# MotherBoard.net
KiCad netlist of a schematic drawn in Altium Designer
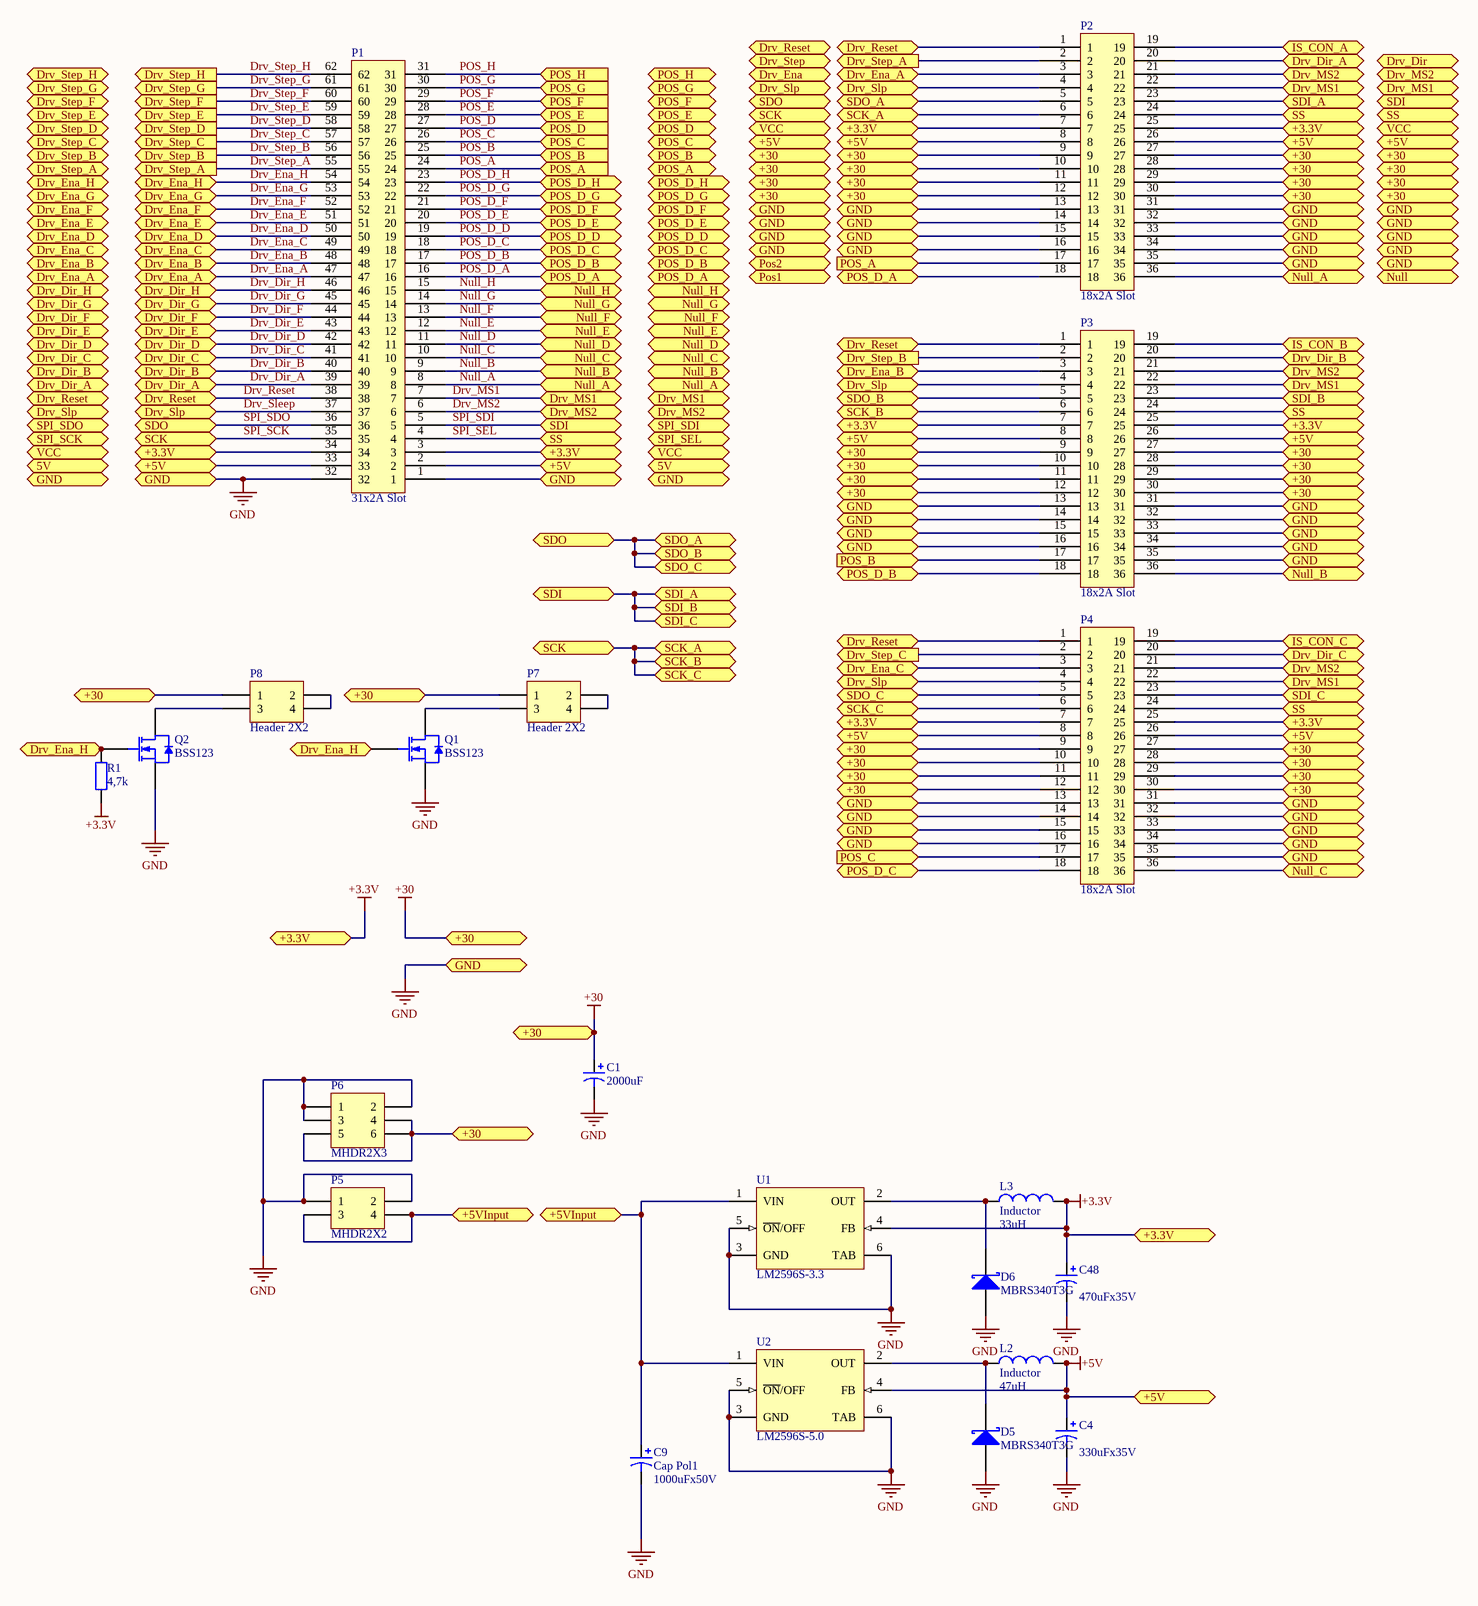
[diagram p0: MotherBoard.SchDoc]

(export (version "E")
  (design (tool "Eeschema 10.0.6"))
  (components
    (comp (ref "C1")
      (value "2000uF")
      (footprint "Cap16x36")
      (description "Polarized Capacitor (Radial)")
      (fields (field (name "Comment") "Cap Pol1") (field (name "PUBLISHER") "Altium Limited"))
      (libsource (lib "Miscellaneous Devices") (part "Cap Pol1"))
    )
    (comp (ref "C4")
      (value "330uFx35V")
      (footprint "Type E")
      (description "Polarized Capacitor (Radial)")
      (fields (field (name "Comment") "Cap Pol1") (field (name "PUBLISHER") "Altium Limited"))
      (libsource (lib "Miscellaneous Devices") (part "Cap Pol1"))
    )
    (comp (ref "C9")
      (value "Cap Pol1")
      (footprint "Cap13x25")
      (description "Polarized Capacitor (Radial)")
      (fields (field (name "ALTIUM_VALUE") "1000uFx50V") (field (name "PUBLISHER") "Altium Limited"))
      (libsource (lib "Miscellaneous Devices") (part "Cap Pol1"))
    )
    (comp (ref "C48")
      (value "470uFx35V")
      (footprint "Type E")
      (description "Polarized Capacitor (Radial)")
      (fields (field (name "Comment") "Cap Pol1") (field (name "PUBLISHER") "Altium Limited"))
      (libsource (lib "Miscellaneous Devices") (part "Cap Pol1"))
    )
    (comp (ref "D5")
      (value "MBRS340T3G")
      (footprint "SMC wbody")
      (description "Schottky Rectifier")
      (fields (field (name "PUBLISHER") "Altium Limited"))
      (libsource (lib "IR Rectifier - Schottky") (part "30BQ100"))
    )
    (comp (ref "D6")
      (value "MBRS340T3G")
      (footprint "SMC wbody")
      (description "Schottky Rectifier")
      (fields (field (name "PUBLISHER") "Altium Limited"))
      (libsource (lib "IR Rectifier - Schottky") (part "30BQ100"))
    )
    (comp (ref "L2")
      (value "Inductor")
      (footprint "CDRH127/LD")
      (fields (field (name "ALTIUM_VALUE") "47uH") (field (name "PUBLISHER") "Altium Limited"))
      (libsource (lib "Miscellaneous Devices") (part "Inductor"))
    )
    (comp (ref "L3")
      (value "Inductor")
      (footprint "CDRH127/LD")
      (fields (field (name "ALTIUM_VALUE") "33uH") (field (name "PUBLISHER") "Altium Limited"))
      (libsource (lib "Miscellaneous Devices") (part "Inductor"))
    )
    (comp (ref "P1")
      (value "31x2A Slot")
      (footprint "SL-62A")
      (description "31x2 Slot")
      (libsource (lib "Slot") (part "31x2A Slot"))
    )
    (comp (ref "P2") (value "18x2A Slot") (footprint "SL-36A") (libsource (lib "Slot") (part "18x2A Slot")))
    (comp (ref "P3") (value "18x2A Slot") (footprint "SL-36A") (libsource (lib "Slot") (part "18x2A Slot")))
    (comp (ref "P4") (value "18x2A Slot") (footprint "SL-36A") (libsource (lib "Slot") (part "18x2A Slot")))
    (comp (ref "P5")
      (value "MHDR2X2")
      (footprint "MF-2x2")
      (description "Header, 2-Pin, Dual row")
      (fields (field (name "PUBLISHER") "Altium Limited"))
      (libsource (lib "Miscellaneous Connectors") (part "MHDR2X2"))
    )
    (comp (ref "P6")
      (value "MHDR2X3")
      (footprint "MF-2x3")
      (description "Header, 3-Pin, Dual row")
      (fields (field (name "PUBLISHER") "Altium Limited"))
      (libsource (lib "Miscellaneous Connectors") (part "MHDR2X3"))
    )
    (comp (ref "P7")
      (value "Header 2X2")
      (footprint "HDR2X2")
      (description "Header, 2-Pin, Dual row")
      (fields (field (name "PUBLISHER") "Altium Limited"))
      (libsource (lib "Miscellaneous Connectors") (part "Header 2X2"))
    )
    (comp (ref "P8")
      (value "Header 2X2")
      (footprint "HDR2X2")
      (description "Header, 2-Pin, Dual row")
      (fields (field (name "PUBLISHER") "Altium Limited"))
      (libsource (lib "Miscellaneous Connectors") (part "Header 2X2"))
    )
    (comp (ref "Q1")
      (value "BSS123")
      (footprint "SOT23_N")
      (description "N-channel Enhancement Mode Vertical D-MOSFET")
      (fields (field (name "PUBLISHER") "Altium Limited"))
      (libsource (lib "Philips Discrete MOSFET - Low Power") (part "BSS123"))
    )
    (comp (ref "Q2")
      (value "BSS123")
      (footprint "SOT23_N")
      (description "N-channel Enhancement Mode Vertical D-MOSFET")
      (fields (field (name "PUBLISHER") "Altium Limited"))
      (libsource (lib "Philips Discrete MOSFET - Low Power") (part "BSS123"))
    )
    (comp (ref "R1")
      (value "4,7k")
      (footprint "RESC2012M")
      (description "Resistor")
      (fields (field (name "Comment") "Res2") (field (name "PUBLISHER") "Altium Limited"))
      (libsource (lib "Miscellaneous Devices") (part "Res2"))
    )
    (comp (ref "U1")
      (value "LM2596S-3.3")
      (footprint "TS5B_N")
      (description "SIMPLE SWITCHER Power Converter 150 KHz 3A Step-Down Voltage Regulator")
      (fields
        (field (name "MANUFACTURER") "National Semiconductor")
        (field (name "DIGIKEYPARTNUMBER") "LM2596S-3.3-ND")
        (field (name "PUBLISHER") "Altium Limited")
      )
      (libsource (lib "NSC Switcher") (part "LM2596S-3.3"))
    )
    (comp (ref "U2")
      (value "LM2596S-5.0")
      (footprint "TS5B_N")
      (description "SIMPLE SWITCHER Power Converter 150 KHz 3A Step-Down Voltage Regulator")
      (fields
        (field (name "MANUFACTURER") "National Semiconductor")
        (field (name "DIGIKEYPARTNUMBER") "LM2596S-5.0-ND")
        (field (name "PUBLISHER") "Altium Limited")
      )
      (libsource (lib "NSC Switcher") (part "LM2596S-5.0"))
    )
  )
  (nets
    (net (code "1") (name "+3.3V") (class "Default")
      (node (ref "C48") (pin "1") (pinfunction "1_1") (pintype "passive"))
      (node (ref "L3") (pin "2") (pinfunction "2_2") (pintype "passive"))
      (node (ref "P1") (pin "3") (pinfunction "3_3") (pintype "passive"))
      (node (ref "P1") (pin "34") (pinfunction "34_34") (pintype "passive"))
      (node (ref "P2") (pin "25") (pinfunction "25_25") (pintype "passive"))
      (node (ref "P2") (pin "7") (pinfunction "7_7") (pintype "passive"))
      (node (ref "P3") (pin "25") (pinfunction "25_25") (pintype "passive"))
      (node (ref "P3") (pin "7") (pinfunction "7_7") (pintype "passive"))
      (node (ref "P4") (pin "25") (pinfunction "25_25") (pintype "passive"))
      (node (ref "P4") (pin "7") (pinfunction "7_7") (pintype "passive"))
      (node (ref "R1") (pin "2") (pinfunction "2_2") (pintype "passive"))
      (node (ref "U1") (pin "4") (pinfunction "FB_4") (pintype "input"))
    )
    (net (code "2") (name "+5V") (class "Default")
      (node (ref "C4") (pin "1") (pinfunction "1_1") (pintype "passive"))
      (node (ref "L2") (pin "2") (pinfunction "2_2") (pintype "passive"))
      (node (ref "P1") (pin "2") (pinfunction "2_2") (pintype "passive"))
      (node (ref "P1") (pin "33") (pinfunction "33_33") (pintype "passive"))
      (node (ref "P2") (pin "26") (pinfunction "26_26") (pintype "passive"))
      (node (ref "P2") (pin "8") (pinfunction "8_8") (pintype "passive"))
      (node (ref "P3") (pin "26") (pinfunction "26_26") (pintype "passive"))
      (node (ref "P3") (pin "8") (pinfunction "8_8") (pintype "passive"))
      (node (ref "P4") (pin "26") (pinfunction "26_26") (pintype "passive"))
      (node (ref "P4") (pin "8") (pinfunction "8_8") (pintype "passive"))
      (node (ref "U2") (pin "4") (pinfunction "FB_4") (pintype "input"))
    )
    (net (code "3") (name "+30") (class "Default")
      (node (ref "C1") (pin "1") (pinfunction "1_1") (pintype "passive"))
      (node (ref "P2") (pin "10") (pinfunction "10_10") (pintype "passive"))
      (node (ref "P2") (pin "11") (pinfunction "11_11") (pintype "passive"))
      (node (ref "P2") (pin "12") (pinfunction "12_12") (pintype "passive"))
      (node (ref "P2") (pin "27") (pinfunction "27_27") (pintype "passive"))
      (node (ref "P2") (pin "28") (pinfunction "28_28") (pintype "passive"))
      (node (ref "P2") (pin "29") (pinfunction "29_29") (pintype "passive"))
      (node (ref "P2") (pin "30") (pinfunction "30_30") (pintype "passive"))
      (node (ref "P2") (pin "9") (pinfunction "9_9") (pintype "passive"))
      (node (ref "P3") (pin "10") (pinfunction "10_10") (pintype "passive"))
      (node (ref "P3") (pin "11") (pinfunction "11_11") (pintype "passive"))
      (node (ref "P3") (pin "12") (pinfunction "12_12") (pintype "passive"))
      (node (ref "P3") (pin "27") (pinfunction "27_27") (pintype "passive"))
      (node (ref "P3") (pin "28") (pinfunction "28_28") (pintype "passive"))
      (node (ref "P3") (pin "29") (pinfunction "29_29") (pintype "passive"))
      (node (ref "P3") (pin "30") (pinfunction "30_30") (pintype "passive"))
      (node (ref "P3") (pin "9") (pinfunction "9_9") (pintype "passive"))
      (node (ref "P4") (pin "10") (pinfunction "10_10") (pintype "passive"))
      (node (ref "P4") (pin "11") (pinfunction "11_11") (pintype "passive"))
      (node (ref "P4") (pin "12") (pinfunction "12_12") (pintype "passive"))
      (node (ref "P4") (pin "27") (pinfunction "27_27") (pintype "passive"))
      (node (ref "P4") (pin "28") (pinfunction "28_28") (pintype "passive"))
      (node (ref "P4") (pin "29") (pinfunction "29_29") (pintype "passive"))
      (node (ref "P4") (pin "30") (pinfunction "30_30") (pintype "passive"))
      (node (ref "P4") (pin "9") (pinfunction "9_9") (pintype "passive"))
      (node (ref "P6") (pin "4") (pinfunction "4_4") (pintype "passive"))
      (node (ref "P6") (pin "5") (pinfunction "5_5") (pintype "passive"))
      (node (ref "P6") (pin "6") (pinfunction "6_6") (pintype "passive"))
      (node (ref "P7") (pin "1") (pinfunction "1_1") (pintype "passive"))
      (node (ref "P8") (pin "1") (pinfunction "1_1") (pintype "passive"))
    )
    (net (code "4") (name "/+5VInput") (class "Default")
      (node (ref "C9") (pin "1") (pinfunction "1_1") (pintype "passive"))
      (node (ref "P5") (pin "3") (pinfunction "3_3") (pintype "passive"))
      (node (ref "P5") (pin "4") (pinfunction "4_4") (pintype "passive"))
      (node (ref "U1") (pin "1") (pinfunction "VIN_1") (pintype "power_in"))
      (node (ref "U2") (pin "1") (pinfunction "VIN_1") (pintype "power_in"))
    )
    (net (code "7") (name "/Drv_Dir_A") (class "Default")
      (node (ref "P1") (pin "39") (pinfunction "39_39") (pintype "passive"))
      (node (ref "P2") (pin "20") (pinfunction "20_20") (pintype "passive"))
    )
    (net (code "8") (name "/Drv_Dir_B") (class "Default")
      (node (ref "P1") (pin "40") (pinfunction "40_40") (pintype "passive"))
      (node (ref "P3") (pin "20") (pinfunction "20_20") (pintype "passive"))
    )
    (net (code "9") (name "/Drv_Dir_C") (class "Default")
      (node (ref "P1") (pin "41") (pinfunction "41_41") (pintype "passive"))
      (node (ref "P4") (pin "20") (pinfunction "20_20") (pintype "passive"))
    )
    (net (code "10") (name "/Drv_Dir_D") (class "Default")
      (node (ref "P1") (pin "42") (pinfunction "42_42") (pintype "passive"))
    )
    (net (code "11") (name "/Drv_Dir_E") (class "Default")
      (node (ref "P1") (pin "43") (pinfunction "43_43") (pintype "passive"))
    )
    (net (code "12") (name "/Drv_Dir_F") (class "Default")
      (node (ref "P1") (pin "44") (pinfunction "44_44") (pintype "passive"))
    )
    (net (code "13") (name "/Drv_Dir_G") (class "Default")
      (node (ref "P1") (pin "45") (pinfunction "45_45") (pintype "passive"))
    )
    (net (code "14") (name "/Drv_Dir_H") (class "Default")
      (node (ref "P1") (pin "46") (pinfunction "46_46") (pintype "passive"))
    )
    (net (code "16") (name "/Drv_Ena_A") (class "Default")
      (node (ref "P1") (pin "47") (pinfunction "47_47") (pintype "passive"))
      (node (ref "P2") (pin "3") (pinfunction "3_3") (pintype "passive"))
    )
    (net (code "17") (name "/Drv_Ena_B") (class "Default")
      (node (ref "P1") (pin "48") (pinfunction "48_48") (pintype "passive"))
      (node (ref "P3") (pin "3") (pinfunction "3_3") (pintype "passive"))
    )
    (net (code "18") (name "/Drv_Ena_C") (class "Default")
      (node (ref "P1") (pin "49") (pinfunction "49_49") (pintype "passive"))
      (node (ref "P4") (pin "3") (pinfunction "3_3") (pintype "passive"))
    )
    (net (code "19") (name "/Drv_Ena_D") (class "Default")
      (node (ref "P1") (pin "50") (pinfunction "50_50") (pintype "passive"))
    )
    (net (code "20") (name "/Drv_Ena_E") (class "Default")
      (node (ref "P1") (pin "51") (pinfunction "51_51") (pintype "passive"))
    )
    (net (code "21") (name "/Drv_Ena_F") (class "Default")
      (node (ref "P1") (pin "52") (pinfunction "52_52") (pintype "passive"))
    )
    (net (code "22") (name "/Drv_Ena_G") (class "Default")
      (node (ref "P1") (pin "53") (pinfunction "53_53") (pintype "passive"))
    )
    (net (code "23") (name "/Drv_Ena_H") (class "Default")
      (node (ref "P1") (pin "54") (pinfunction "54_54") (pintype "passive"))
      (node (ref "Q1") (pin "1") (pinfunction "G_1") (pintype "passive"))
      (node (ref "Q2") (pin "1") (pinfunction "G_1") (pintype "passive"))
      (node (ref "R1") (pin "1") (pinfunction "1_1") (pintype "passive"))
    )
    (net (code "24") (name "/Drv_MS1") (class "Default")
      (node (ref "P1") (pin "7") (pinfunction "7_7") (pintype "passive"))
      (node (ref "P2") (pin "22") (pinfunction "22_22") (pintype "passive"))
      (node (ref "P3") (pin "22") (pinfunction "22_22") (pintype "passive"))
      (node (ref "P4") (pin "22") (pinfunction "22_22") (pintype "passive"))
    )
    (net (code "25") (name "/Drv_MS2") (class "Default")
      (node (ref "P1") (pin "6") (pinfunction "6_6") (pintype "passive"))
      (node (ref "P2") (pin "21") (pinfunction "21_21") (pintype "passive"))
      (node (ref "P3") (pin "21") (pinfunction "21_21") (pintype "passive"))
      (node (ref "P4") (pin "21") (pinfunction "21_21") (pintype "passive"))
    )
    (net (code "26") (name "/Drv_Reset") (class "Default")
      (node (ref "P1") (pin "38") (pinfunction "38_38") (pintype "passive"))
      (node (ref "P2") (pin "1") (pinfunction "1_1") (pintype "passive"))
      (node (ref "P3") (pin "1") (pinfunction "1_1") (pintype "passive"))
      (node (ref "P4") (pin "1") (pinfunction "1_1") (pintype "passive"))
    )
    (net (code "27") (name "/Drv_Sleep") (class "Default")
      (node (ref "P1") (pin "37") (pinfunction "37_37") (pintype "passive"))
      (node (ref "P2") (pin "4") (pinfunction "4_4") (pintype "passive"))
      (node (ref "P3") (pin "4") (pinfunction "4_4") (pintype "passive"))
      (node (ref "P4") (pin "4") (pinfunction "4_4") (pintype "passive"))
    )
    (net (code "29") (name "/Drv_Step_A") (class "Default")
      (node (ref "P1") (pin "55") (pinfunction "55_55") (pintype "passive"))
      (node (ref "P2") (pin "2") (pinfunction "2_2") (pintype "passive"))
    )
    (net (code "30") (name "/Drv_Step_B") (class "Default")
      (node (ref "P1") (pin "56") (pinfunction "56_56") (pintype "passive"))
      (node (ref "P3") (pin "2") (pinfunction "2_2") (pintype "passive"))
    )
    (net (code "31") (name "/Drv_Step_C") (class "Default")
      (node (ref "P1") (pin "57") (pinfunction "57_57") (pintype "passive"))
      (node (ref "P4") (pin "2") (pinfunction "2_2") (pintype "passive"))
    )
    (net (code "32") (name "/Drv_Step_D") (class "Default")
      (node (ref "P1") (pin "58") (pinfunction "58_58") (pintype "passive"))
    )
    (net (code "33") (name "/Drv_Step_E") (class "Default")
      (node (ref "P1") (pin "59") (pinfunction "59_59") (pintype "passive"))
    )
    (net (code "34") (name "/Drv_Step_F") (class "Default")
      (node (ref "P1") (pin "60") (pinfunction "60_60") (pintype "passive"))
    )
    (net (code "35") (name "/Drv_Step_G") (class "Default")
      (node (ref "P1") (pin "61") (pinfunction "61_61") (pintype "passive"))
    )
    (net (code "36") (name "/Drv_Step_H") (class "Default")
      (node (ref "P1") (pin "62") (pinfunction "62_62") (pintype "passive"))
    )
    (net (code "37") (name "/IS_CON_A") (class "Default")
      (node (ref "P2") (pin "19") (pinfunction "19_19") (pintype "passive"))
    )
    (net (code "38") (name "/IS_CON_B") (class "Default")
      (node (ref "P3") (pin "19") (pinfunction "19_19") (pintype "passive"))
    )
    (net (code "39") (name "/IS_CON_C") (class "Default")
      (node (ref "P4") (pin "19") (pinfunction "19_19") (pintype "passive"))
    )
    (net (code "41") (name "/Null_A") (class "Default")
      (node (ref "P1") (pin "8") (pinfunction "8_8") (pintype "passive"))
      (node (ref "P2") (pin "36") (pinfunction "36_36") (pintype "passive"))
    )
    (net (code "42") (name "/Null_B") (class "Default")
      (node (ref "P1") (pin "9") (pinfunction "9_9") (pintype "passive"))
      (node (ref "P3") (pin "36") (pinfunction "36_36") (pintype "passive"))
    )
    (net (code "43") (name "/Null_C") (class "Default")
      (node (ref "P1") (pin "10") (pinfunction "10_10") (pintype "passive"))
      (node (ref "P4") (pin "36") (pinfunction "36_36") (pintype "passive"))
    )
    (net (code "44") (name "/Null_D") (class "Default")
      (node (ref "P1") (pin "11") (pinfunction "11_11") (pintype "passive"))
    )
    (net (code "45") (name "/Null_E") (class "Default")
      (node (ref "P1") (pin "12") (pinfunction "12_12") (pintype "passive"))
    )
    (net (code "46") (name "/Null_F") (class "Default")
      (node (ref "P1") (pin "13") (pinfunction "13_13") (pintype "passive"))
    )
    (net (code "47") (name "/Null_G") (class "Default")
      (node (ref "P1") (pin "14") (pinfunction "14_14") (pintype "passive"))
    )
    (net (code "48") (name "/Null_H") (class "Default")
      (node (ref "P1") (pin "15") (pinfunction "15_15") (pintype "passive"))
    )
    (net (code "49") (name "/POS_A") (class "Default")
      (node (ref "P1") (pin "24") (pinfunction "24_24") (pintype "passive"))
      (node (ref "P2") (pin "17") (pinfunction "17_17") (pintype "passive"))
    )
    (net (code "50") (name "/POS_B") (class "Default")
      (node (ref "P1") (pin "25") (pinfunction "25_25") (pintype "passive"))
      (node (ref "P3") (pin "17") (pinfunction "17_17") (pintype "passive"))
    )
    (net (code "51") (name "/POS_C") (class "Default")
      (node (ref "P1") (pin "26") (pinfunction "26_26") (pintype "passive"))
      (node (ref "P4") (pin "17") (pinfunction "17_17") (pintype "passive"))
    )
    (net (code "52") (name "/POS_D") (class "Default")
      (node (ref "P1") (pin "27") (pinfunction "27_27") (pintype "passive"))
    )
    (net (code "53") (name "/POS_D_A") (class "Default")
      (node (ref "P1") (pin "16") (pinfunction "16_16") (pintype "passive"))
      (node (ref "P2") (pin "18") (pinfunction "18_18") (pintype "passive"))
    )
    (net (code "54") (name "/POS_D_B") (class "Default")
      (node (ref "P1") (pin "17") (pinfunction "17_17") (pintype "passive"))
      (node (ref "P3") (pin "18") (pinfunction "18_18") (pintype "passive"))
    )
    (net (code "55") (name "/POS_D_C") (class "Default")
      (node (ref "P1") (pin "18") (pinfunction "18_18") (pintype "passive"))
      (node (ref "P4") (pin "18") (pinfunction "18_18") (pintype "passive"))
    )
    (net (code "56") (name "/POS_D_D") (class "Default")
      (node (ref "P1") (pin "19") (pinfunction "19_19") (pintype "passive"))
    )
    (net (code "57") (name "/POS_D_E") (class "Default")
      (node (ref "P1") (pin "20") (pinfunction "20_20") (pintype "passive"))
    )
    (net (code "58") (name "/POS_D_F") (class "Default")
      (node (ref "P1") (pin "21") (pinfunction "21_21") (pintype "passive"))
    )
    (net (code "59") (name "/POS_D_G") (class "Default")
      (node (ref "P1") (pin "22") (pinfunction "22_22") (pintype "passive"))
    )
    (net (code "60") (name "/POS_D_H") (class "Default")
      (node (ref "P1") (pin "23") (pinfunction "23_23") (pintype "passive"))
    )
    (net (code "61") (name "/POS_E") (class "Default")
      (node (ref "P1") (pin "28") (pinfunction "28_28") (pintype "passive"))
    )
    (net (code "62") (name "/POS_F") (class "Default")
      (node (ref "P1") (pin "29") (pinfunction "29_29") (pintype "passive"))
    )
    (net (code "63") (name "/POS_G") (class "Default")
      (node (ref "P1") (pin "30") (pinfunction "30_30") (pintype "passive"))
    )
    (net (code "64") (name "/POS_H") (class "Default")
      (node (ref "P1") (pin "31") (pinfunction "31_31") (pintype "passive"))
    )
    (net (code "67") (name "/SPI_SCK") (class "Default")
      (node (ref "P1") (pin "35") (pinfunction "35_35") (pintype "passive"))
      (node (ref "P2") (pin "6") (pinfunction "6_6") (pintype "passive"))
      (node (ref "P3") (pin "6") (pinfunction "6_6") (pintype "passive"))
      (node (ref "P4") (pin "6") (pinfunction "6_6") (pintype "passive"))
    )
    (net (code "68") (name "/SPI_SDI") (class "Default")
      (node (ref "P1") (pin "5") (pinfunction "5_5") (pintype "passive"))
      (node (ref "P2") (pin "23") (pinfunction "23_23") (pintype "passive"))
      (node (ref "P3") (pin "23") (pinfunction "23_23") (pintype "passive"))
      (node (ref "P4") (pin "23") (pinfunction "23_23") (pintype "passive"))
    )
    (net (code "69") (name "/SPI_SDO") (class "Default")
      (node (ref "P1") (pin "36") (pinfunction "36_36") (pintype "passive"))
      (node (ref "P2") (pin "5") (pinfunction "5_5") (pintype "passive"))
      (node (ref "P3") (pin "5") (pinfunction "5_5") (pintype "passive"))
      (node (ref "P4") (pin "5") (pinfunction "5_5") (pintype "passive"))
    )
    (net (code "70") (name "/SPI_SEL") (class "Default")
      (node (ref "P1") (pin "4") (pinfunction "4_4") (pintype "passive"))
      (node (ref "P2") (pin "24") (pinfunction "24_24") (pintype "passive"))
      (node (ref "P3") (pin "24") (pinfunction "24_24") (pintype "passive"))
      (node (ref "P4") (pin "24") (pinfunction "24_24") (pintype "passive"))
    )
    (net (code "72") (name "GND") (class "Default")
      (node (ref "C1") (pin "2") (pinfunction "2_2") (pintype "passive"))
      (node (ref "C4") (pin "2") (pinfunction "2_2") (pintype "passive"))
      (node (ref "C48") (pin "2") (pinfunction "2_2") (pintype "passive"))
      (node (ref "C9") (pin "2") (pinfunction "2_2") (pintype "passive"))
      (node (ref "D5") (pin "1") (pinfunction "A_1") (pintype "passive"))
      (node (ref "D6") (pin "1") (pinfunction "A_1") (pintype "passive"))
      (node (ref "P1") (pin "1") (pinfunction "1_1") (pintype "passive"))
      (node (ref "P1") (pin "32") (pinfunction "32_32") (pintype "passive"))
      (node (ref "P2") (pin "13") (pinfunction "13_13") (pintype "passive"))
      (node (ref "P2") (pin "14") (pinfunction "14_14") (pintype "passive"))
      (node (ref "P2") (pin "15") (pinfunction "15_15") (pintype "passive"))
      (node (ref "P2") (pin "16") (pinfunction "16_16") (pintype "passive"))
      (node (ref "P2") (pin "31") (pinfunction "31_31") (pintype "passive"))
      (node (ref "P2") (pin "32") (pinfunction "32_32") (pintype "passive"))
      (node (ref "P2") (pin "33") (pinfunction "33_33") (pintype "passive"))
      (node (ref "P2") (pin "34") (pinfunction "34_34") (pintype "passive"))
      (node (ref "P2") (pin "35") (pinfunction "35_35") (pintype "passive"))
      (node (ref "P3") (pin "13") (pinfunction "13_13") (pintype "passive"))
      (node (ref "P3") (pin "14") (pinfunction "14_14") (pintype "passive"))
      (node (ref "P3") (pin "15") (pinfunction "15_15") (pintype "passive"))
      (node (ref "P3") (pin "16") (pinfunction "16_16") (pintype "passive"))
      (node (ref "P3") (pin "31") (pinfunction "31_31") (pintype "passive"))
      (node (ref "P3") (pin "32") (pinfunction "32_32") (pintype "passive"))
      (node (ref "P3") (pin "33") (pinfunction "33_33") (pintype "passive"))
      (node (ref "P3") (pin "34") (pinfunction "34_34") (pintype "passive"))
      (node (ref "P3") (pin "35") (pinfunction "35_35") (pintype "passive"))
      (node (ref "P4") (pin "13") (pinfunction "13_13") (pintype "passive"))
      (node (ref "P4") (pin "14") (pinfunction "14_14") (pintype "passive"))
      (node (ref "P4") (pin "15") (pinfunction "15_15") (pintype "passive"))
      (node (ref "P4") (pin "16") (pinfunction "16_16") (pintype "passive"))
      (node (ref "P4") (pin "31") (pinfunction "31_31") (pintype "passive"))
      (node (ref "P4") (pin "32") (pinfunction "32_32") (pintype "passive"))
      (node (ref "P4") (pin "33") (pinfunction "33_33") (pintype "passive"))
      (node (ref "P4") (pin "34") (pinfunction "34_34") (pintype "passive"))
      (node (ref "P4") (pin "35") (pinfunction "35_35") (pintype "passive"))
      (node (ref "P5") (pin "1") (pinfunction "1_1") (pintype "passive"))
      (node (ref "P5") (pin "2") (pinfunction "2_2") (pintype "passive"))
      (node (ref "P6") (pin "1") (pinfunction "1_1") (pintype "passive"))
      (node (ref "P6") (pin "2") (pinfunction "2_2") (pintype "passive"))
      (node (ref "P6") (pin "3") (pinfunction "3_3") (pintype "passive"))
      (node (ref "Q1") (pin "2") (pinfunction "S_2") (pintype "passive"))
      (node (ref "Q2") (pin "2") (pinfunction "S_2") (pintype "passive"))
      (node (ref "U1") (pin "3") (pinfunction "GND_3") (pintype "power_in"))
      (node (ref "U1") (pin "5") (pinfunction "~{ON}/OFF_5") (pintype "input"))
      (node (ref "U1") (pin "6") (pinfunction "TAB_6") (pintype "power_in"))
      (node (ref "U2") (pin "3") (pinfunction "GND_3") (pintype "power_in"))
      (node (ref "U2") (pin "5") (pinfunction "~{ON}/OFF_5") (pintype "input"))
      (node (ref "U2") (pin "6") (pinfunction "TAB_6") (pintype "power_in"))
    )
    (net (code "73") (name "Net-(D5-K)") (class "Default")
      (node (ref "D5") (pin "2") (pinfunction "K_2") (pintype "passive"))
      (node (ref "L2") (pin "1") (pinfunction "1_1") (pintype "passive"))
      (node (ref "U2") (pin "2") (pinfunction "OUT_2") (pintype "power_in"))
    )
    (net (code "74") (name "Net-(D6-K)") (class "Default")
      (node (ref "D6") (pin "2") (pinfunction "K_2") (pintype "passive"))
      (node (ref "L3") (pin "1") (pinfunction "1_1") (pintype "passive"))
      (node (ref "U1") (pin "2") (pinfunction "OUT_2") (pintype "power_in"))
    )
    (net (code "75") (name "Net-(P7-Pad2)") (class "Default")
      (node (ref "P7") (pin "2") (pinfunction "2_2") (pintype "passive"))
      (node (ref "P7") (pin "4") (pinfunction "4_4") (pintype "passive"))
    )
    (net (code "76") (name "Net-(P8-Pad2)") (class "Default")
      (node (ref "P8") (pin "2") (pinfunction "2_2") (pintype "passive"))
      (node (ref "P8") (pin "4") (pinfunction "4_4") (pintype "passive"))
    )
    (net (code "77") (name "Net-(Q1-D)") (class "Default")
      (node (ref "P7") (pin "3") (pinfunction "3_3") (pintype "passive"))
      (node (ref "Q1") (pin "3") (pinfunction "D_3") (pintype "passive"))
    )
    (net (code "78") (name "Net-(Q2-D)") (class "Default")
      (node (ref "P8") (pin "3") (pinfunction "3_3") (pintype "passive"))
      (node (ref "Q2") (pin "3") (pinfunction "D_3") (pintype "passive"))
    )
  )
)
